# lv_io_solenoid_drv.net
KiCad netlist of a schematic drawn in Altium Designer
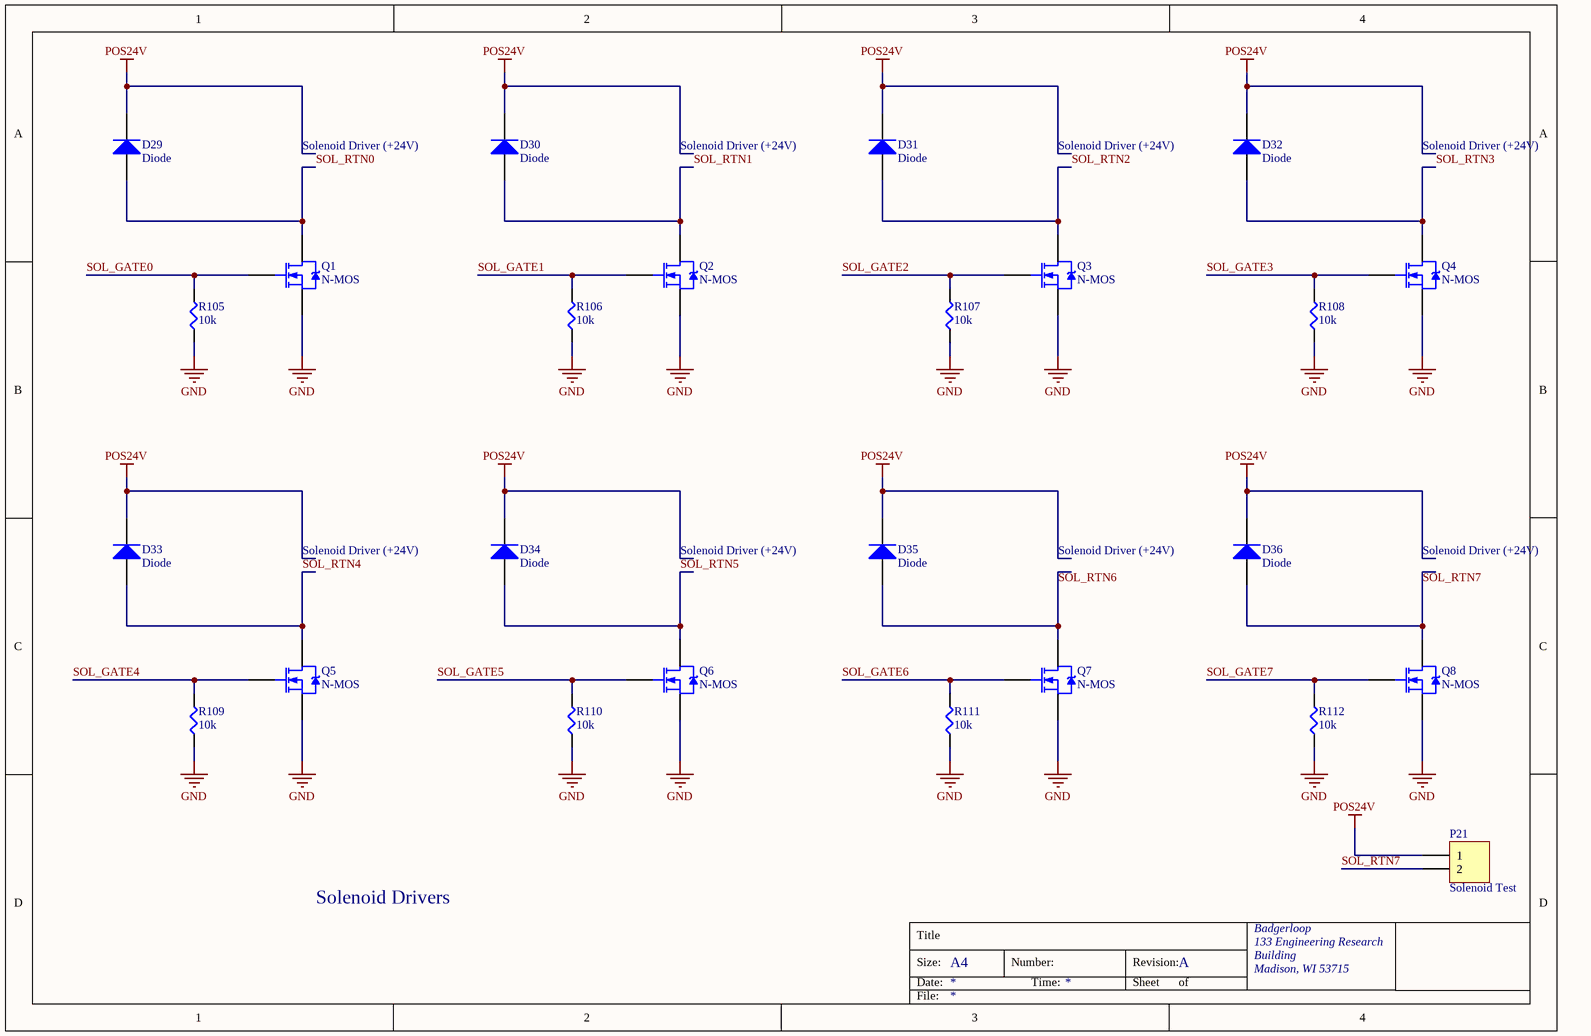
[diagram p0: lv_io_solenoid_drv.SchDoc]

(export (version "E")
  (design (tool "Eeschema 10.0.6"))
  (components
    (comp (ref "D29")
      (value "Diode")
      (footprint "SODFL360X110-2N")
      (description "DIODE GEN PURP 200V 2A SOD123FL")
      (fields (field (name "MANUFACTURER") "ON SEMI"))
      (libsource (lib "temp") (part "DIODE STD"))
    )
    (comp (ref "D30")
      (value "Diode")
      (footprint "SODFL360X110-2N")
      (description "DIODE GEN PURP 200V 2A SOD123FL")
      (fields (field (name "MANUFACTURER") "ON SEMI"))
      (libsource (lib "temp") (part "DIODE STD"))
    )
    (comp (ref "D31")
      (value "Diode")
      (footprint "SODFL360X110-2N")
      (description "DIODE GEN PURP 200V 2A SOD123FL")
      (fields (field (name "MANUFACTURER") "ON SEMI"))
      (libsource (lib "temp") (part "DIODE STD"))
    )
    (comp (ref "D32")
      (value "Diode")
      (footprint "SODFL360X110-2N")
      (description "DIODE GEN PURP 200V 2A SOD123FL")
      (fields (field (name "MANUFACTURER") "ON SEMI"))
      (libsource (lib "temp") (part "DIODE STD"))
    )
    (comp (ref "D33")
      (value "Diode")
      (footprint "SODFL360X110-2N")
      (description "DIODE GEN PURP 200V 2A SOD123FL")
      (fields (field (name "MANUFACTURER") "ON SEMI"))
      (libsource (lib "temp") (part "DIODE STD"))
    )
    (comp (ref "D34")
      (value "Diode")
      (footprint "SODFL360X110-2N")
      (description "DIODE GEN PURP 200V 2A SOD123FL")
      (fields (field (name "MANUFACTURER") "ON SEMI"))
      (libsource (lib "temp") (part "DIODE STD"))
    )
    (comp (ref "D35")
      (value "Diode")
      (footprint "SODFL360X110-2N")
      (description "DIODE GEN PURP 200V 2A SOD123FL")
      (fields (field (name "MANUFACTURER") "ON SEMI"))
      (libsource (lib "temp") (part "DIODE STD"))
    )
    (comp (ref "D36")
      (value "Diode")
      (footprint "SODFL360X110-2N")
      (description "DIODE GEN PURP 200V 2A SOD123FL")
      (fields (field (name "MANUFACTURER") "ON SEMI"))
      (libsource (lib "temp") (part "DIODE STD"))
    )
    (comp (ref "P21")
      (value "Solenoid Test")
      (footprint "Pin Header 1x2 TH Pitch 2.54mm")
      (description "Header, 2-Pin")
      (fields (field (name "PUBLISHER") "Altium Limited"))
      (libsource (lib "connector") (part "Header 2"))
    )
    (comp (ref "Q1")
      (value "N-MOS")
      (footprint "DPAK228P991X238-3N")
      (description "N-Channel Power MOSFET, 12 A, 60 V")
      (fields (field (name "MANUFACTURER") "ON SEMI"))
      (libsource (lib "ic") (part "N-MOS"))
    )
    (comp (ref "Q2")
      (value "N-MOS")
      (footprint "DPAK228P991X238-3N")
      (description "N-Channel Power MOSFET, 12 A, 60 V")
      (fields (field (name "MANUFACTURER") "ON SEMI"))
      (libsource (lib "ic") (part "N-MOS"))
    )
    (comp (ref "Q3")
      (value "N-MOS")
      (footprint "DPAK228P991X238-3N")
      (description "N-Channel Power MOSFET, 12 A, 60 V")
      (fields (field (name "MANUFACTURER") "ON SEMI"))
      (libsource (lib "ic") (part "N-MOS"))
    )
    (comp (ref "Q4")
      (value "N-MOS")
      (footprint "DPAK228P991X238-3N")
      (description "N-Channel Power MOSFET, 12 A, 60 V")
      (fields (field (name "MANUFACTURER") "ON SEMI"))
      (libsource (lib "ic") (part "N-MOS"))
    )
    (comp (ref "Q5")
      (value "N-MOS")
      (footprint "DPAK228P991X238-3N")
      (description "N-Channel Power MOSFET, 12 A, 60 V")
      (fields (field (name "MANUFACTURER") "ON SEMI"))
      (libsource (lib "ic") (part "N-MOS"))
    )
    (comp (ref "Q6")
      (value "N-MOS")
      (footprint "DPAK228P991X238-3N")
      (description "N-Channel Power MOSFET, 12 A, 60 V")
      (fields (field (name "MANUFACTURER") "ON SEMI"))
      (libsource (lib "ic") (part "N-MOS"))
    )
    (comp (ref "Q7")
      (value "N-MOS")
      (footprint "DPAK228P991X238-3N")
      (description "N-Channel Power MOSFET, 12 A, 60 V")
      (fields (field (name "MANUFACTURER") "ON SEMI"))
      (libsource (lib "ic") (part "N-MOS"))
    )
    (comp (ref "Q8")
      (value "N-MOS")
      (footprint "DPAK228P991X238-3N")
      (description "N-Channel Power MOSFET, 12 A, 60 V")
      (fields (field (name "MANUFACTURER") "ON SEMI"))
      (libsource (lib "ic") (part "N-MOS"))
    )
    (comp (ref "R105")
      (value "10k")
      (footprint "SMD-0402-RES")
      (description "RES SMD 10K OHM 0.5% 1/16W 0402")
      (fields
        (field (name "PART NUMBER") "ERJ-2RHD1002X")
        (field (name "DIGI-KEY PART NUMBER") "P15984CT-ND")
      )
      (libsource (lib "resistor") (part "ERJ-2RHD1002X"))
    )
    (comp (ref "R106")
      (value "10k")
      (footprint "SMD-0402-RES")
      (description "RES SMD 10K OHM 0.5% 1/16W 0402")
      (fields
        (field (name "PART NUMBER") "ERJ-2RHD1002X")
        (field (name "DIGI-KEY PART NUMBER") "P15984CT-ND")
      )
      (libsource (lib "resistor") (part "ERJ-2RHD1002X"))
    )
    (comp (ref "R107")
      (value "10k")
      (footprint "SMD-0402-RES")
      (description "RES SMD 10K OHM 0.5% 1/16W 0402")
      (fields
        (field (name "PART NUMBER") "ERJ-2RHD1002X")
        (field (name "DIGI-KEY PART NUMBER") "P15984CT-ND")
      )
      (libsource (lib "resistor") (part "ERJ-2RHD1002X"))
    )
    (comp (ref "R108")
      (value "10k")
      (footprint "SMD-0402-RES")
      (description "RES SMD 10K OHM 0.5% 1/16W 0402")
      (fields
        (field (name "PART NUMBER") "ERJ-2RHD1002X")
        (field (name "DIGI-KEY PART NUMBER") "P15984CT-ND")
      )
      (libsource (lib "resistor") (part "ERJ-2RHD1002X"))
    )
    (comp (ref "R109")
      (value "10k")
      (footprint "SMD-0402-RES")
      (description "RES SMD 10K OHM 0.5% 1/16W 0402")
      (fields
        (field (name "PART NUMBER") "ERJ-2RHD1002X")
        (field (name "DIGI-KEY PART NUMBER") "P15984CT-ND")
      )
      (libsource (lib "resistor") (part "ERJ-2RHD1002X"))
    )
    (comp (ref "R110")
      (value "10k")
      (footprint "SMD-0402-RES")
      (description "RES SMD 10K OHM 0.5% 1/16W 0402")
      (fields
        (field (name "PART NUMBER") "ERJ-2RHD1002X")
        (field (name "DIGI-KEY PART NUMBER") "P15984CT-ND")
      )
      (libsource (lib "resistor") (part "ERJ-2RHD1002X"))
    )
    (comp (ref "R111")
      (value "10k")
      (footprint "SMD-0402-RES")
      (description "RES SMD 10K OHM 0.5% 1/16W 0402")
      (fields
        (field (name "PART NUMBER") "ERJ-2RHD1002X")
        (field (name "DIGI-KEY PART NUMBER") "P15984CT-ND")
      )
      (libsource (lib "resistor") (part "ERJ-2RHD1002X"))
    )
    (comp (ref "R112")
      (value "10k")
      (footprint "SMD-0402-RES")
      (description "RES SMD 10K OHM 0.5% 1/16W 0402")
      (fields
        (field (name "PART NUMBER") "ERJ-2RHD1002X")
        (field (name "DIGI-KEY PART NUMBER") "P15984CT-ND")
      )
      (libsource (lib "resistor") (part "ERJ-2RHD1002X"))
    )
  )
  (nets
    (net (code "1") (name "/SOL_GATE0") (class "Default")
      (node (ref "Q1") (pin "1") (pinfunction "G_1") (pintype "passive"))
      (node (ref "R105") (pin "2") (pinfunction "2_2") (pintype "passive"))
    )
    (net (code "2") (name "/SOL_GATE1") (class "Default")
      (node (ref "Q2") (pin "1") (pinfunction "G_1") (pintype "passive"))
      (node (ref "R106") (pin "2") (pinfunction "2_2") (pintype "passive"))
    )
    (net (code "3") (name "/SOL_GATE2") (class "Default")
      (node (ref "Q3") (pin "1") (pinfunction "G_1") (pintype "passive"))
      (node (ref "R107") (pin "2") (pinfunction "2_2") (pintype "passive"))
    )
    (net (code "4") (name "/SOL_GATE3") (class "Default")
      (node (ref "Q4") (pin "1") (pinfunction "G_1") (pintype "passive"))
      (node (ref "R108") (pin "2") (pinfunction "2_2") (pintype "passive"))
    )
    (net (code "5") (name "/SOL_GATE4") (class "Default")
      (node (ref "Q5") (pin "1") (pinfunction "G_1") (pintype "passive"))
      (node (ref "R109") (pin "2") (pinfunction "2_2") (pintype "passive"))
    )
    (net (code "6") (name "/SOL_GATE5") (class "Default")
      (node (ref "Q6") (pin "1") (pinfunction "G_1") (pintype "passive"))
      (node (ref "R110") (pin "2") (pinfunction "2_2") (pintype "passive"))
    )
    (net (code "7") (name "/SOL_GATE6") (class "Default")
      (node (ref "Q7") (pin "1") (pinfunction "G_1") (pintype "passive"))
      (node (ref "R111") (pin "2") (pinfunction "2_2") (pintype "passive"))
    )
    (net (code "8") (name "/SOL_GATE7") (class "Default")
      (node (ref "Q8") (pin "1") (pinfunction "G_1") (pintype "passive"))
      (node (ref "R112") (pin "2") (pinfunction "2_2") (pintype "passive"))
    )
    (net (code "9") (name "/SOL_RTN0") (class "Default")
      (node (ref "D29") (pin "1") (pinfunction "A_1") (pintype "passive"))
      (node (ref "Q1") (pin "4") (pinfunction "D_4") (pintype "passive"))
    )
    (net (code "10") (name "/SOL_RTN1") (class "Default")
      (node (ref "D30") (pin "1") (pinfunction "A_1") (pintype "passive"))
      (node (ref "Q2") (pin "4") (pinfunction "D_4") (pintype "passive"))
    )
    (net (code "11") (name "/SOL_RTN2") (class "Default")
      (node (ref "D31") (pin "1") (pinfunction "A_1") (pintype "passive"))
      (node (ref "Q3") (pin "4") (pinfunction "D_4") (pintype "passive"))
    )
    (net (code "12") (name "/SOL_RTN3") (class "Default")
      (node (ref "D32") (pin "1") (pinfunction "A_1") (pintype "passive"))
      (node (ref "Q4") (pin "4") (pinfunction "D_4") (pintype "passive"))
    )
    (net (code "13") (name "/SOL_RTN4") (class "Default")
      (node (ref "D33") (pin "1") (pinfunction "A_1") (pintype "passive"))
      (node (ref "Q5") (pin "4") (pinfunction "D_4") (pintype "passive"))
    )
    (net (code "14") (name "/SOL_RTN5") (class "Default")
      (node (ref "D34") (pin "1") (pinfunction "A_1") (pintype "passive"))
      (node (ref "Q6") (pin "4") (pinfunction "D_4") (pintype "passive"))
    )
    (net (code "15") (name "/SOL_RTN6") (class "Default")
      (node (ref "D35") (pin "1") (pinfunction "A_1") (pintype "passive"))
      (node (ref "Q7") (pin "4") (pinfunction "D_4") (pintype "passive"))
    )
    (net (code "16") (name "/SOL_RTN7") (class "Default")
      (node (ref "D36") (pin "1") (pinfunction "A_1") (pintype "passive"))
      (node (ref "P21") (pin "2") (pinfunction "2_2") (pintype "passive"))
      (node (ref "Q8") (pin "4") (pinfunction "D_4") (pintype "passive"))
    )
    (net (code "17") (name "GND") (class "Default")
      (node (ref "Q1") (pin "3") (pinfunction "S_3") (pintype "passive"))
      (node (ref "Q2") (pin "3") (pinfunction "S_3") (pintype "passive"))
      (node (ref "Q3") (pin "3") (pinfunction "S_3") (pintype "passive"))
      (node (ref "Q4") (pin "3") (pinfunction "S_3") (pintype "passive"))
      (node (ref "Q5") (pin "3") (pinfunction "S_3") (pintype "passive"))
      (node (ref "Q6") (pin "3") (pinfunction "S_3") (pintype "passive"))
      (node (ref "Q7") (pin "3") (pinfunction "S_3") (pintype "passive"))
      (node (ref "Q8") (pin "3") (pinfunction "S_3") (pintype "passive"))
      (node (ref "R105") (pin "1") (pinfunction "1_1") (pintype "passive"))
      (node (ref "R106") (pin "1") (pinfunction "1_1") (pintype "passive"))
      (node (ref "R107") (pin "1") (pinfunction "1_1") (pintype "passive"))
      (node (ref "R108") (pin "1") (pinfunction "1_1") (pintype "passive"))
      (node (ref "R109") (pin "1") (pinfunction "1_1") (pintype "passive"))
      (node (ref "R110") (pin "1") (pinfunction "1_1") (pintype "passive"))
      (node (ref "R111") (pin "1") (pinfunction "1_1") (pintype "passive"))
      (node (ref "R112") (pin "1") (pinfunction "1_1") (pintype "passive"))
    )
    (net (code "18") (name "POS24V") (class "Default")
      (node (ref "D29") (pin "2") (pinfunction "K_2") (pintype "passive"))
      (node (ref "D30") (pin "2") (pinfunction "K_2") (pintype "passive"))
      (node (ref "D31") (pin "2") (pinfunction "K_2") (pintype "passive"))
      (node (ref "D32") (pin "2") (pinfunction "K_2") (pintype "passive"))
      (node (ref "D33") (pin "2") (pinfunction "K_2") (pintype "passive"))
      (node (ref "D34") (pin "2") (pinfunction "K_2") (pintype "passive"))
      (node (ref "D35") (pin "2") (pinfunction "K_2") (pintype "passive"))
      (node (ref "D36") (pin "2") (pinfunction "K_2") (pintype "passive"))
      (node (ref "P21") (pin "1") (pinfunction "1_1") (pintype "passive"))
    )
  )
)
